# revA.net
KiCad netlist of a schematic drawn in EAGLE
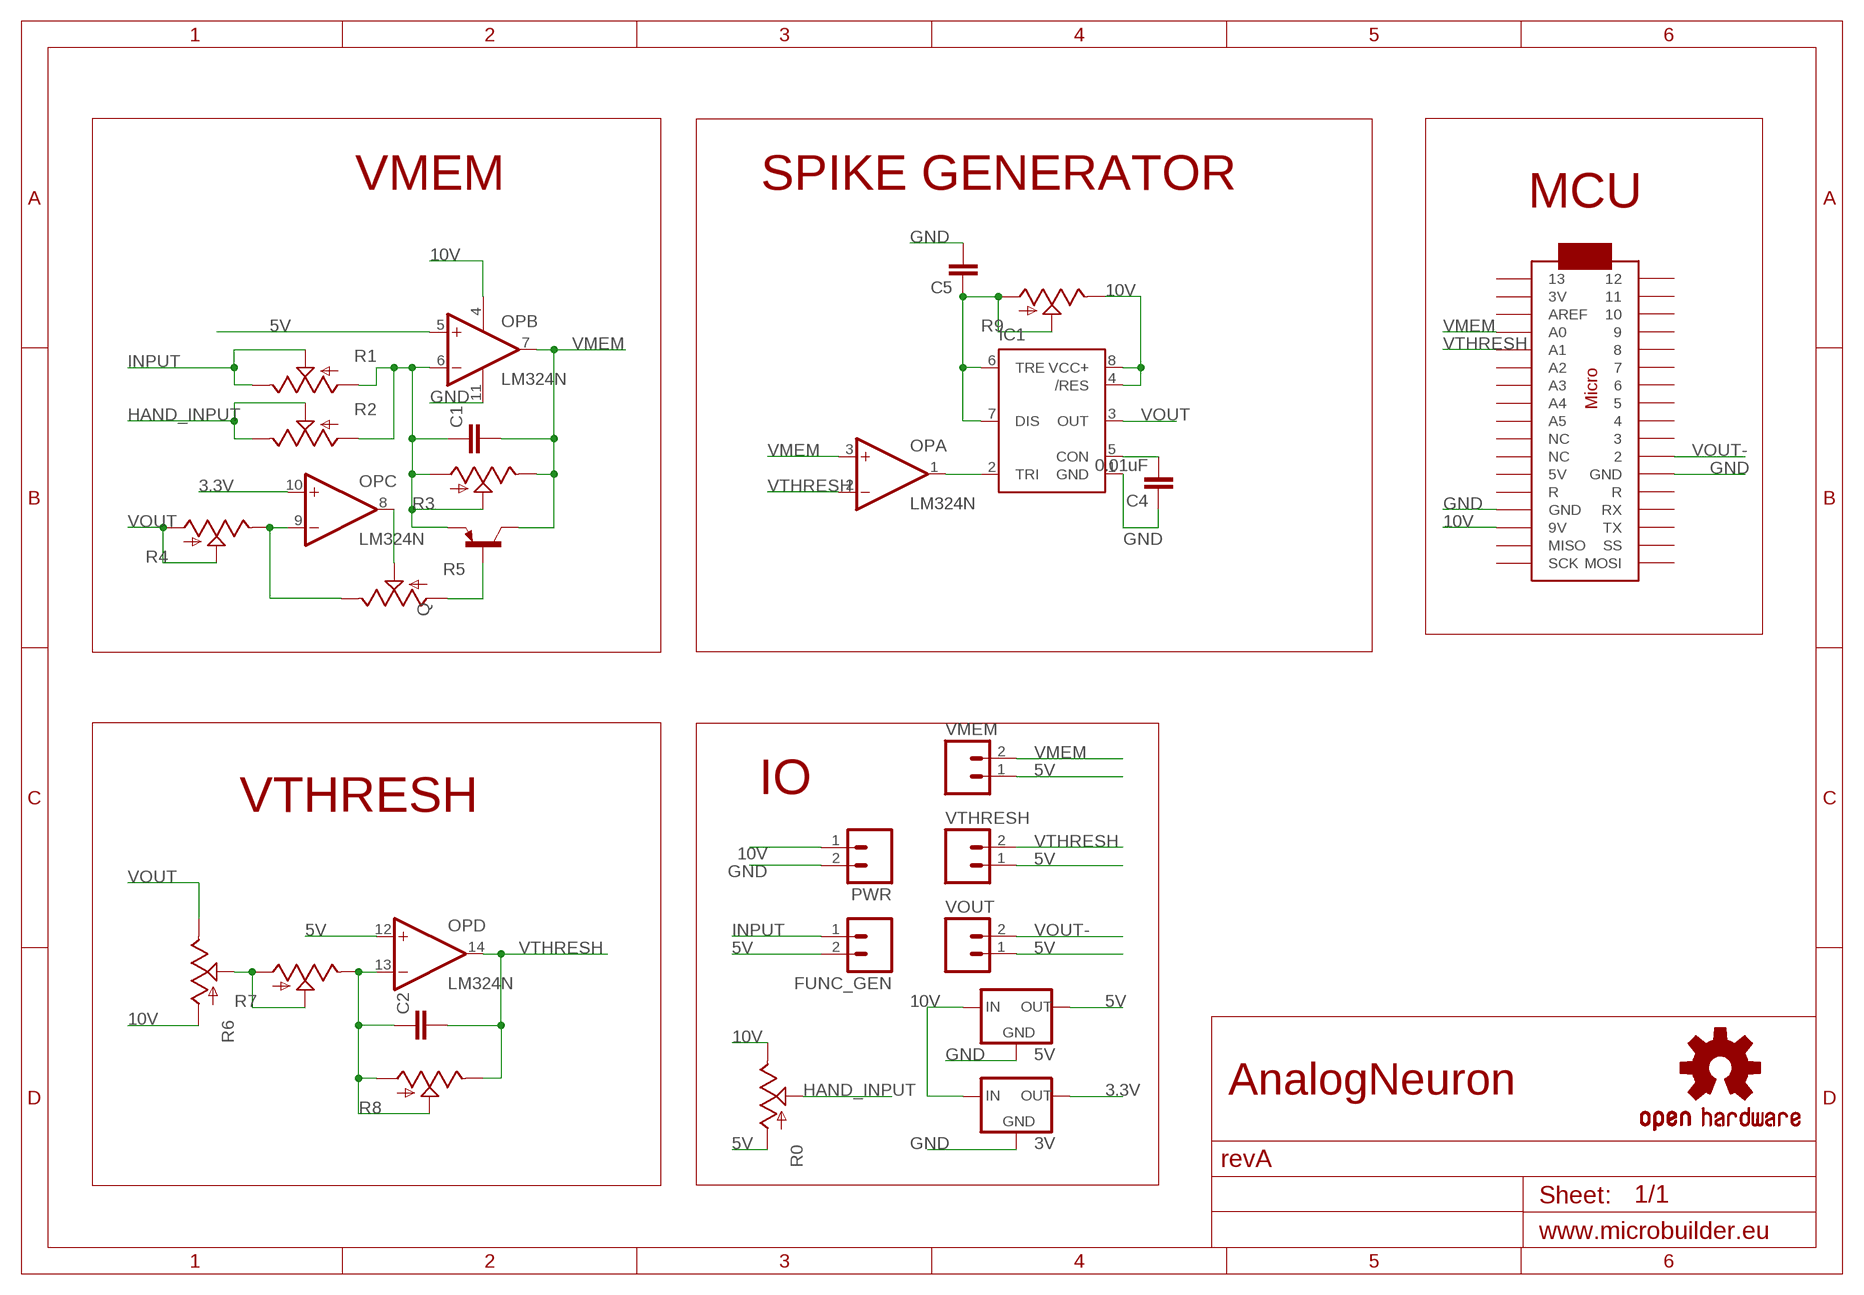
[diagram p0: schematic, sheet 1]

(export (version "E")
  (design (tool "Eeschema 10.0.6"))
  (components
    (comp (ref "3V")
      (value "78LXX")
      (footprint "eagle-import:78LXX")
      (libsource (lib "eagle-import") (part "78LXX"))
    )
    (comp (ref "5V")
      (value "78LXX")
      (footprint "eagle-import:78LXX")
      (libsource (lib "eagle-import") (part "78LXX"))
    )
    (comp (ref "C1")
      (value "CAPPTH1")
      (footprint "eagle-import:CAP-PTH-5MM")
      (libsource (lib "eagle-import") (part "CAPPTH1"))
    )
    (comp (ref "C2")
      (value "CAPPTH1")
      (footprint "eagle-import:CAP-PTH-5MM")
      (libsource (lib "eagle-import") (part "CAPPTH1"))
    )
    (comp (ref "C4")
      (value "0.01uF")
      (footprint "eagle-import:CAP-PTH-5MM")
      (libsource (lib "eagle-import") (part "CAPPTH1"))
    )
    (comp (ref "C5")
      (value "CAPPTH1")
      (footprint "eagle-import:CAP-PTH-5MM")
      (libsource (lib "eagle-import") (part "CAPPTH1"))
    )
    (comp (ref "FUNC_GEN")
      (value "M023.5MM")
      (footprint "eagle-import:SCREWTERMINAL-3.5MM-2")
      (libsource (lib "eagle-import") (part "M023.5MM"))
    )
    (comp (ref "IC1")
      (value "NE555KIT")
      (footprint "eagle-import:DIP08-KIT")
      (libsource (lib "eagle-import") (part "NE555KIT"))
    )
    (comp (ref "LOGO1")
      (value "OSHW-LOGOL-TOP")
      (footprint "eagle-import:OSHW_LOGO_L_TOP")
      (libsource (lib "eagle-import") (part "OSHW-LOGOL-TOP"))
    )
    (comp (ref "OP")
      (value "LM324N")
      (footprint "eagle-import:DIL14")
      (libsource (lib "eagle-import") (part "LM324N"))
    )
    (comp (ref "PWR")
      (value "M023.5MM")
      (footprint "eagle-import:SCREWTERMINAL-3.5MM-2")
      (libsource (lib "eagle-import") (part "M023.5MM"))
    )
    (comp (ref "Q")
      (value "2N3906-PNP-TO92-EBC")
      (footprint "eagle-import:TO92-EBC")
      (libsource (lib "eagle-import") (part "-PNP-TO92-EBC2N3906"))
    )
    (comp (ref "R0")
      (value "POT")
      (footprint "eagle-import:ALPS_POT")
      (libsource (lib "eagle-import") (part "POT"))
    )
    (comp (ref "R1")
      (value "POT")
      (footprint "eagle-import:ALPS_POT")
      (libsource (lib "eagle-import") (part "POT"))
    )
    (comp (ref "R2")
      (value "POT")
      (footprint "eagle-import:ALPS_POT")
      (libsource (lib "eagle-import") (part "POT"))
    )
    (comp (ref "R3")
      (value "POT")
      (footprint "eagle-import:ALPS_POT")
      (libsource (lib "eagle-import") (part "POT"))
    )
    (comp (ref "R4")
      (value "POT")
      (footprint "eagle-import:ALPS_POT")
      (libsource (lib "eagle-import") (part "POT"))
    )
    (comp (ref "R5")
      (value "POT")
      (footprint "eagle-import:ALPS_POT")
      (libsource (lib "eagle-import") (part "POT"))
    )
    (comp (ref "R6")
      (value "POT")
      (footprint "eagle-import:ALPS_POT")
      (libsource (lib "eagle-import") (part "POT"))
    )
    (comp (ref "R7")
      (value "POT")
      (footprint "eagle-import:ALPS_POT")
      (libsource (lib "eagle-import") (part "POT"))
    )
    (comp (ref "R8")
      (value "POT")
      (footprint "eagle-import:ALPS_POT")
      (libsource (lib "eagle-import") (part "POT"))
    )
    (comp (ref "R9")
      (value "POT")
      (footprint "eagle-import:ALPS_POT")
      (libsource (lib "eagle-import") (part "POT"))
    )
    (comp (ref "U$1")
      (value "ARDUINOMICRO")
      (footprint "eagle-import:ARDUINOMICRO")
      (libsource (lib "eagle-import") (part "ARDUINOMICRO"))
    )
    (comp (ref "VMEM")
      (value "M023.5MM")
      (footprint "eagle-import:SCREWTERMINAL-3.5MM-2")
      (libsource (lib "eagle-import") (part "M023.5MM"))
    )
    (comp (ref "VOUT")
      (value "M023.5MM")
      (footprint "eagle-import:SCREWTERMINAL-3.5MM-2")
      (libsource (lib "eagle-import") (part "M023.5MM"))
    )
    (comp (ref "VTHRESH")
      (value "M023.5MM")
      (footprint "eagle-import:SCREWTERMINAL-3.5MM-2")
      (libsource (lib "eagle-import") (part "M023.5MM"))
    )
  )
  (nets
    (net (code "1") (name "/3.3V") (class "Default")
      (node (ref "3V") (pin "OUT") (pinfunction "OUT_OUT") (pintype "passive"))
      (node (ref "OP") (pin "10") (pinfunction "+IN_10") (pintype "input"))
    )
    (net (code "2") (name "/5V") (class "Default")
      (node (ref "5V") (pin "OUT") (pinfunction "OUT_OUT") (pintype "passive"))
      (node (ref "FUNC_GEN") (pin "2") (pinfunction "2_2") (pintype "passive"))
      (node (ref "OP") (pin "12") (pinfunction "+IN_12") (pintype "input"))
      (node (ref "OP") (pin "5") (pinfunction "+IN_5") (pintype "input"))
      (node (ref "R0") (pin "P$3") (pinfunction "A_P$3") (pintype "passive"))
      (node (ref "VMEM") (pin "1") (pinfunction "1_1") (pintype "passive"))
      (node (ref "VOUT") (pin "1") (pinfunction "1_1") (pintype "passive"))
      (node (ref "VTHRESH") (pin "1") (pinfunction "1_1") (pintype "passive"))
    )
    (net (code "3") (name "/10V") (class "Default")
      (node (ref "3V") (pin "IN") (pinfunction "IN_IN") (pintype "input"))
      (node (ref "5V") (pin "IN") (pinfunction "IN_IN") (pintype "input"))
      (node (ref "IC1") (pin "4") (pinfunction "/RES_4") (pintype "input"))
      (node (ref "IC1") (pin "8") (pinfunction "VCC+_8") (pintype "power_in"))
      (node (ref "OP") (pin "4") (pinfunction "V+_4") (pintype "power_in"))
      (node (ref "PWR") (pin "1") (pinfunction "1_1") (pintype "passive"))
      (node (ref "R0") (pin "P$1") (pinfunction "E_P$1") (pintype "passive"))
      (node (ref "R6") (pin "P$3") (pinfunction "A_P$3") (pintype "passive"))
      (node (ref "R9") (pin "P$1") (pinfunction "E_P$1") (pintype "passive"))
      (node (ref "U$1") (pin "P$20") (pinfunction "9V_P$20") (pintype "bidirectional"))
    )
    (net (code "4") (name "/GND") (class "Default")
      (node (ref "3V") (pin "GND") (pinfunction "GND_GND") (pintype "input"))
      (node (ref "5V") (pin "GND") (pinfunction "GND_GND") (pintype "input"))
      (node (ref "C4") (pin "1") (pinfunction "1_1") (pintype "passive"))
      (node (ref "C5") (pin "2") (pinfunction "2_2") (pintype "passive"))
      (node (ref "IC1") (pin "1") (pinfunction "GND_1") (pintype "power_in"))
      (node (ref "OP") (pin "11") (pinfunction "V-_11") (pintype "power_in"))
      (node (ref "PWR") (pin "2") (pinfunction "2_2") (pintype "passive"))
      (node (ref "U$1") (pin "P$12") (pinfunction "GND_P$12") (pintype "bidirectional"))
      (node (ref "U$1") (pin "P$21") (pinfunction "GND_P$21") (pintype "bidirectional"))
    )
    (net (code "5") (name "/HAND_INPUT") (class "Default")
      (node (ref "R0") (pin "P$2") (pinfunction "S_P$2") (pintype "passive"))
      (node (ref "R2") (pin "P$1") (pinfunction "E_P$1") (pintype "passive"))
      (node (ref "R2") (pin "P$2") (pinfunction "S_P$2") (pintype "passive"))
    )
    (net (code "6") (name "/INPUT") (class "Default")
      (node (ref "FUNC_GEN") (pin "1") (pinfunction "1_1") (pintype "passive"))
      (node (ref "R1") (pin "P$1") (pinfunction "E_P$1") (pintype "passive"))
      (node (ref "R1") (pin "P$2") (pinfunction "S_P$2") (pintype "passive"))
    )
    (net (code "7") (name "/VMEM") (class "Default")
      (node (ref "C1") (pin "2") (pinfunction "2_2") (pintype "passive"))
      (node (ref "OP") (pin "3") (pinfunction "+IN_3") (pintype "input"))
      (node (ref "OP") (pin "7") (pinfunction "OUT_7") (pintype "output"))
      (node (ref "Q") (pin "C") (pinfunction "C_C") (pintype "passive"))
      (node (ref "R3") (pin "P$1") (pinfunction "E_P$1") (pintype "passive"))
      (node (ref "U$1") (pin "P$31") (pinfunction "A0_P$31") (pintype "bidirectional"))
      (node (ref "VMEM") (pin "2") (pinfunction "2_2") (pintype "passive"))
    )
    (net (code "8") (name "/VOUT") (class "Default")
      (node (ref "IC1") (pin "3") (pinfunction "OUT_3") (pintype "output"))
      (node (ref "R4") (pin "P$2") (pinfunction "S_P$2") (pintype "passive"))
      (node (ref "R4") (pin "P$3") (pinfunction "A_P$3") (pintype "passive"))
      (node (ref "R6") (pin "P$1") (pinfunction "E_P$1") (pintype "passive"))
    )
    (net (code "9") (name "/VOUT-") (class "Default")
      (node (ref "OP") (pin "8") (pinfunction "OUT_8") (pintype "output"))
      (node (ref "R5") (pin "P$2") (pinfunction "S_P$2") (pintype "passive"))
      (node (ref "U$1") (pin "P$11") (pinfunction "2_P$11") (pintype "bidirectional"))
      (node (ref "VOUT") (pin "2") (pinfunction "2_2") (pintype "passive"))
    )
    (net (code "10") (name "/VTHRESH") (class "Default")
      (node (ref "C2") (pin "2") (pinfunction "2_2") (pintype "passive"))
      (node (ref "OP") (pin "14") (pinfunction "OUT_14") (pintype "output"))
      (node (ref "OP") (pin "2") (pinfunction "-IN_2") (pintype "input"))
      (node (ref "R8") (pin "P$1") (pinfunction "E_P$1") (pintype "passive"))
      (node (ref "U$1") (pin "P$30") (pinfunction "A1_P$30") (pintype "bidirectional"))
      (node (ref "VTHRESH") (pin "2") (pinfunction "2_2") (pintype "passive"))
    )
    (net (code "11") (name "Net-(IC1-CON)") (class "Default")
      (node (ref "C4") (pin "2") (pinfunction "2_2") (pintype "passive"))
      (node (ref "IC1") (pin "5") (pinfunction "CON_5") (pintype "input"))
    )
    (net (code "12") (name "Net-(IC1-DIS)") (class "Default")
      (node (ref "C5") (pin "1") (pinfunction "1_1") (pintype "passive"))
      (node (ref "IC1") (pin "6") (pinfunction "TRE_6") (pintype "input"))
      (node (ref "IC1") (pin "7") (pinfunction "DIS_7") (pintype "input"))
      (node (ref "R9") (pin "P$2") (pinfunction "S_P$2") (pintype "passive"))
      (node (ref "R9") (pin "P$3") (pinfunction "A_P$3") (pintype "passive"))
    )
    (net (code "13") (name "Net-(IC1-TRI)") (class "Default")
      (node (ref "IC1") (pin "2") (pinfunction "TRI_2") (pintype "input"))
      (node (ref "OP") (pin "1") (pinfunction "OUT_1") (pintype "output"))
    )
    (net (code "14") (name "Net-(OPB--IN)") (class "Default")
      (node (ref "C1") (pin "1") (pinfunction "1_1") (pintype "passive"))
      (node (ref "OP") (pin "6") (pinfunction "-IN_6") (pintype "input"))
      (node (ref "Q") (pin "E") (pinfunction "E_E") (pintype "passive"))
      (node (ref "R1") (pin "P$3") (pinfunction "A_P$3") (pintype "passive"))
      (node (ref "R2") (pin "P$3") (pinfunction "A_P$3") (pintype "passive"))
      (node (ref "R3") (pin "P$2") (pinfunction "S_P$2") (pintype "passive"))
      (node (ref "R3") (pin "P$3") (pinfunction "A_P$3") (pintype "passive"))
    )
    (net (code "15") (name "Net-(OPC--IN)") (class "Default")
      (node (ref "OP") (pin "9") (pinfunction "-IN_9") (pintype "input"))
      (node (ref "R4") (pin "P$1") (pinfunction "E_P$1") (pintype "passive"))
      (node (ref "R5") (pin "P$1") (pinfunction "E_P$1") (pintype "passive"))
    )
    (net (code "16") (name "Net-(OPD--IN)") (class "Default")
      (node (ref "C2") (pin "1") (pinfunction "1_1") (pintype "passive"))
      (node (ref "OP") (pin "13") (pinfunction "-IN_13") (pintype "input"))
      (node (ref "R7") (pin "P$1") (pinfunction "E_P$1") (pintype "passive"))
      (node (ref "R8") (pin "P$2") (pinfunction "S_P$2") (pintype "passive"))
      (node (ref "R8") (pin "P$3") (pinfunction "A_P$3") (pintype "passive"))
    )
    (net (code "17") (name "Net-(R5-A)") (class "Default")
      (node (ref "Q") (pin "B") (pinfunction "B_B") (pintype "passive"))
      (node (ref "R5") (pin "P$3") (pinfunction "A_P$3") (pintype "passive"))
    )
    (net (code "18") (name "Net-(R6-S)") (class "Default")
      (node (ref "R6") (pin "P$2") (pinfunction "S_P$2") (pintype "passive"))
      (node (ref "R7") (pin "P$2") (pinfunction "S_P$2") (pintype "passive"))
      (node (ref "R7") (pin "P$3") (pinfunction "A_P$3") (pintype "passive"))
    )
    (net (code "19") (name "unconnected-(U$1-3-PadP$10)") (class "Default")
      (node (ref "U$1") (pin "P$10") (pinfunction "3_P$10") (pintype "bidirectional"))
    )
    (net (code "20") (name "unconnected-(U$1-3V-PadP$33)") (class "Default")
      (node (ref "U$1") (pin "P$33") (pinfunction "3V_P$33") (pintype "bidirectional"))
    )
    (net (code "21") (name "unconnected-(U$1-4-PadP$9)") (class "Default")
      (node (ref "U$1") (pin "P$9") (pinfunction "4_P$9") (pintype "bidirectional"))
    )
    (net (code "22") (name "unconnected-(U$1-5-PadP$8)") (class "Default")
      (node (ref "U$1") (pin "P$8") (pinfunction "5_P$8") (pintype "bidirectional"))
    )
    (net (code "23") (name "unconnected-(U$1-5V-PadP$23)") (class "Default")
      (node (ref "U$1") (pin "P$23") (pinfunction "5V_P$23") (pintype "bidirectional"))
    )
    (net (code "24") (name "unconnected-(U$1-6-PadP$7)") (class "Default")
      (node (ref "U$1") (pin "P$7") (pinfunction "6_P$7") (pintype "bidirectional"))
    )
    (net (code "25") (name "unconnected-(U$1-7-PadP$6)") (class "Default")
      (node (ref "U$1") (pin "P$6") (pinfunction "7_P$6") (pintype "bidirectional"))
    )
    (net (code "26") (name "unconnected-(U$1-8-PadP$5)") (class "Default")
      (node (ref "U$1") (pin "P$5") (pinfunction "8_P$5") (pintype "bidirectional"))
    )
    (net (code "27") (name "unconnected-(U$1-9-PadP$4)") (class "Default")
      (node (ref "U$1") (pin "P$4") (pinfunction "9_P$4") (pintype "bidirectional"))
    )
    (net (code "28") (name "unconnected-(U$1-10-PadP$3)") (class "Default")
      (node (ref "U$1") (pin "P$3") (pinfunction "10_P$3") (pintype "bidirectional"))
    )
    (net (code "29") (name "unconnected-(U$1-11-PadP$2)") (class "Default")
      (node (ref "U$1") (pin "P$2") (pinfunction "11_P$2") (pintype "bidirectional"))
    )
    (net (code "30") (name "unconnected-(U$1-12-PadP$1)") (class "Default")
      (node (ref "U$1") (pin "P$1") (pinfunction "12_P$1") (pintype "bidirectional"))
    )
    (net (code "31") (name "unconnected-(U$1-13-PadP$34)") (class "Default")
      (node (ref "U$1") (pin "P$34") (pinfunction "13_P$34") (pintype "bidirectional"))
    )
    (net (code "32") (name "unconnected-(U$1-A2-PadP$29)") (class "Default")
      (node (ref "U$1") (pin "P$29") (pinfunction "A2_P$29") (pintype "bidirectional"))
    )
    (net (code "33") (name "unconnected-(U$1-A3-PadP$28)") (class "Default")
      (node (ref "U$1") (pin "P$28") (pinfunction "A3_P$28") (pintype "bidirectional"))
    )
    (net (code "34") (name "unconnected-(U$1-A4-PadP$27)") (class "Default")
      (node (ref "U$1") (pin "P$27") (pinfunction "A4_P$27") (pintype "bidirectional"))
    )
    (net (code "35") (name "unconnected-(U$1-A5-PadP$26)") (class "Default")
      (node (ref "U$1") (pin "P$26") (pinfunction "A5_P$26") (pintype "bidirectional"))
    )
    (net (code "36") (name "unconnected-(U$1-AREF-PadP$32)") (class "Default")
      (node (ref "U$1") (pin "P$32") (pinfunction "AREF_P$32") (pintype "bidirectional"))
    )
    (net (code "37") (name "unconnected-(U$1-MISO-PadP$19)") (class "Default")
      (node (ref "U$1") (pin "P$19") (pinfunction "MISO_P$19") (pintype "bidirectional"))
    )
    (net (code "38") (name "unconnected-(U$1-MOSI-PadP$17)") (class "Default")
      (node (ref "U$1") (pin "P$17") (pinfunction "MOSI_P$17") (pintype "bidirectional"))
    )
    (net (code "39") (name "unconnected-(U$1-NC-PadP$24)") (class "Default")
      (node (ref "U$1") (pin "P$24") (pinfunction "NC_P$24") (pintype "bidirectional"))
    )
    (net (code "40") (name "unconnected-(U$1-NC-PadP$25)") (class "Default")
      (node (ref "U$1") (pin "P$25") (pinfunction "NC_P$25") (pintype "bidirectional"))
    )
    (net (code "41") (name "unconnected-(U$1-R-PadP$13)") (class "Default")
      (node (ref "U$1") (pin "P$13") (pinfunction "R_P$13") (pintype "bidirectional"))
    )
    (net (code "42") (name "unconnected-(U$1-R-PadP$22)") (class "Default")
      (node (ref "U$1") (pin "P$22") (pinfunction "R_P$22") (pintype "bidirectional"))
    )
    (net (code "43") (name "unconnected-(U$1-RX-PadP$14)") (class "Default")
      (node (ref "U$1") (pin "P$14") (pinfunction "RX_P$14") (pintype "bidirectional"))
    )
    (net (code "44") (name "unconnected-(U$1-SCK-PadP$18)") (class "Default")
      (node (ref "U$1") (pin "P$18") (pinfunction "SCK_P$18") (pintype "bidirectional"))
    )
    (net (code "45") (name "unconnected-(U$1-SS-PadP$16)") (class "Default")
      (node (ref "U$1") (pin "P$16") (pinfunction "SS_P$16") (pintype "bidirectional"))
    )
    (net (code "46") (name "unconnected-(U$1-TX-PadP$15)") (class "Default")
      (node (ref "U$1") (pin "P$15") (pinfunction "TX_P$15") (pintype "bidirectional"))
    )
  )
)
